# Train_Barrierx7_OPTO.net
KiCad netlist of a schematic drawn in EasyEDA
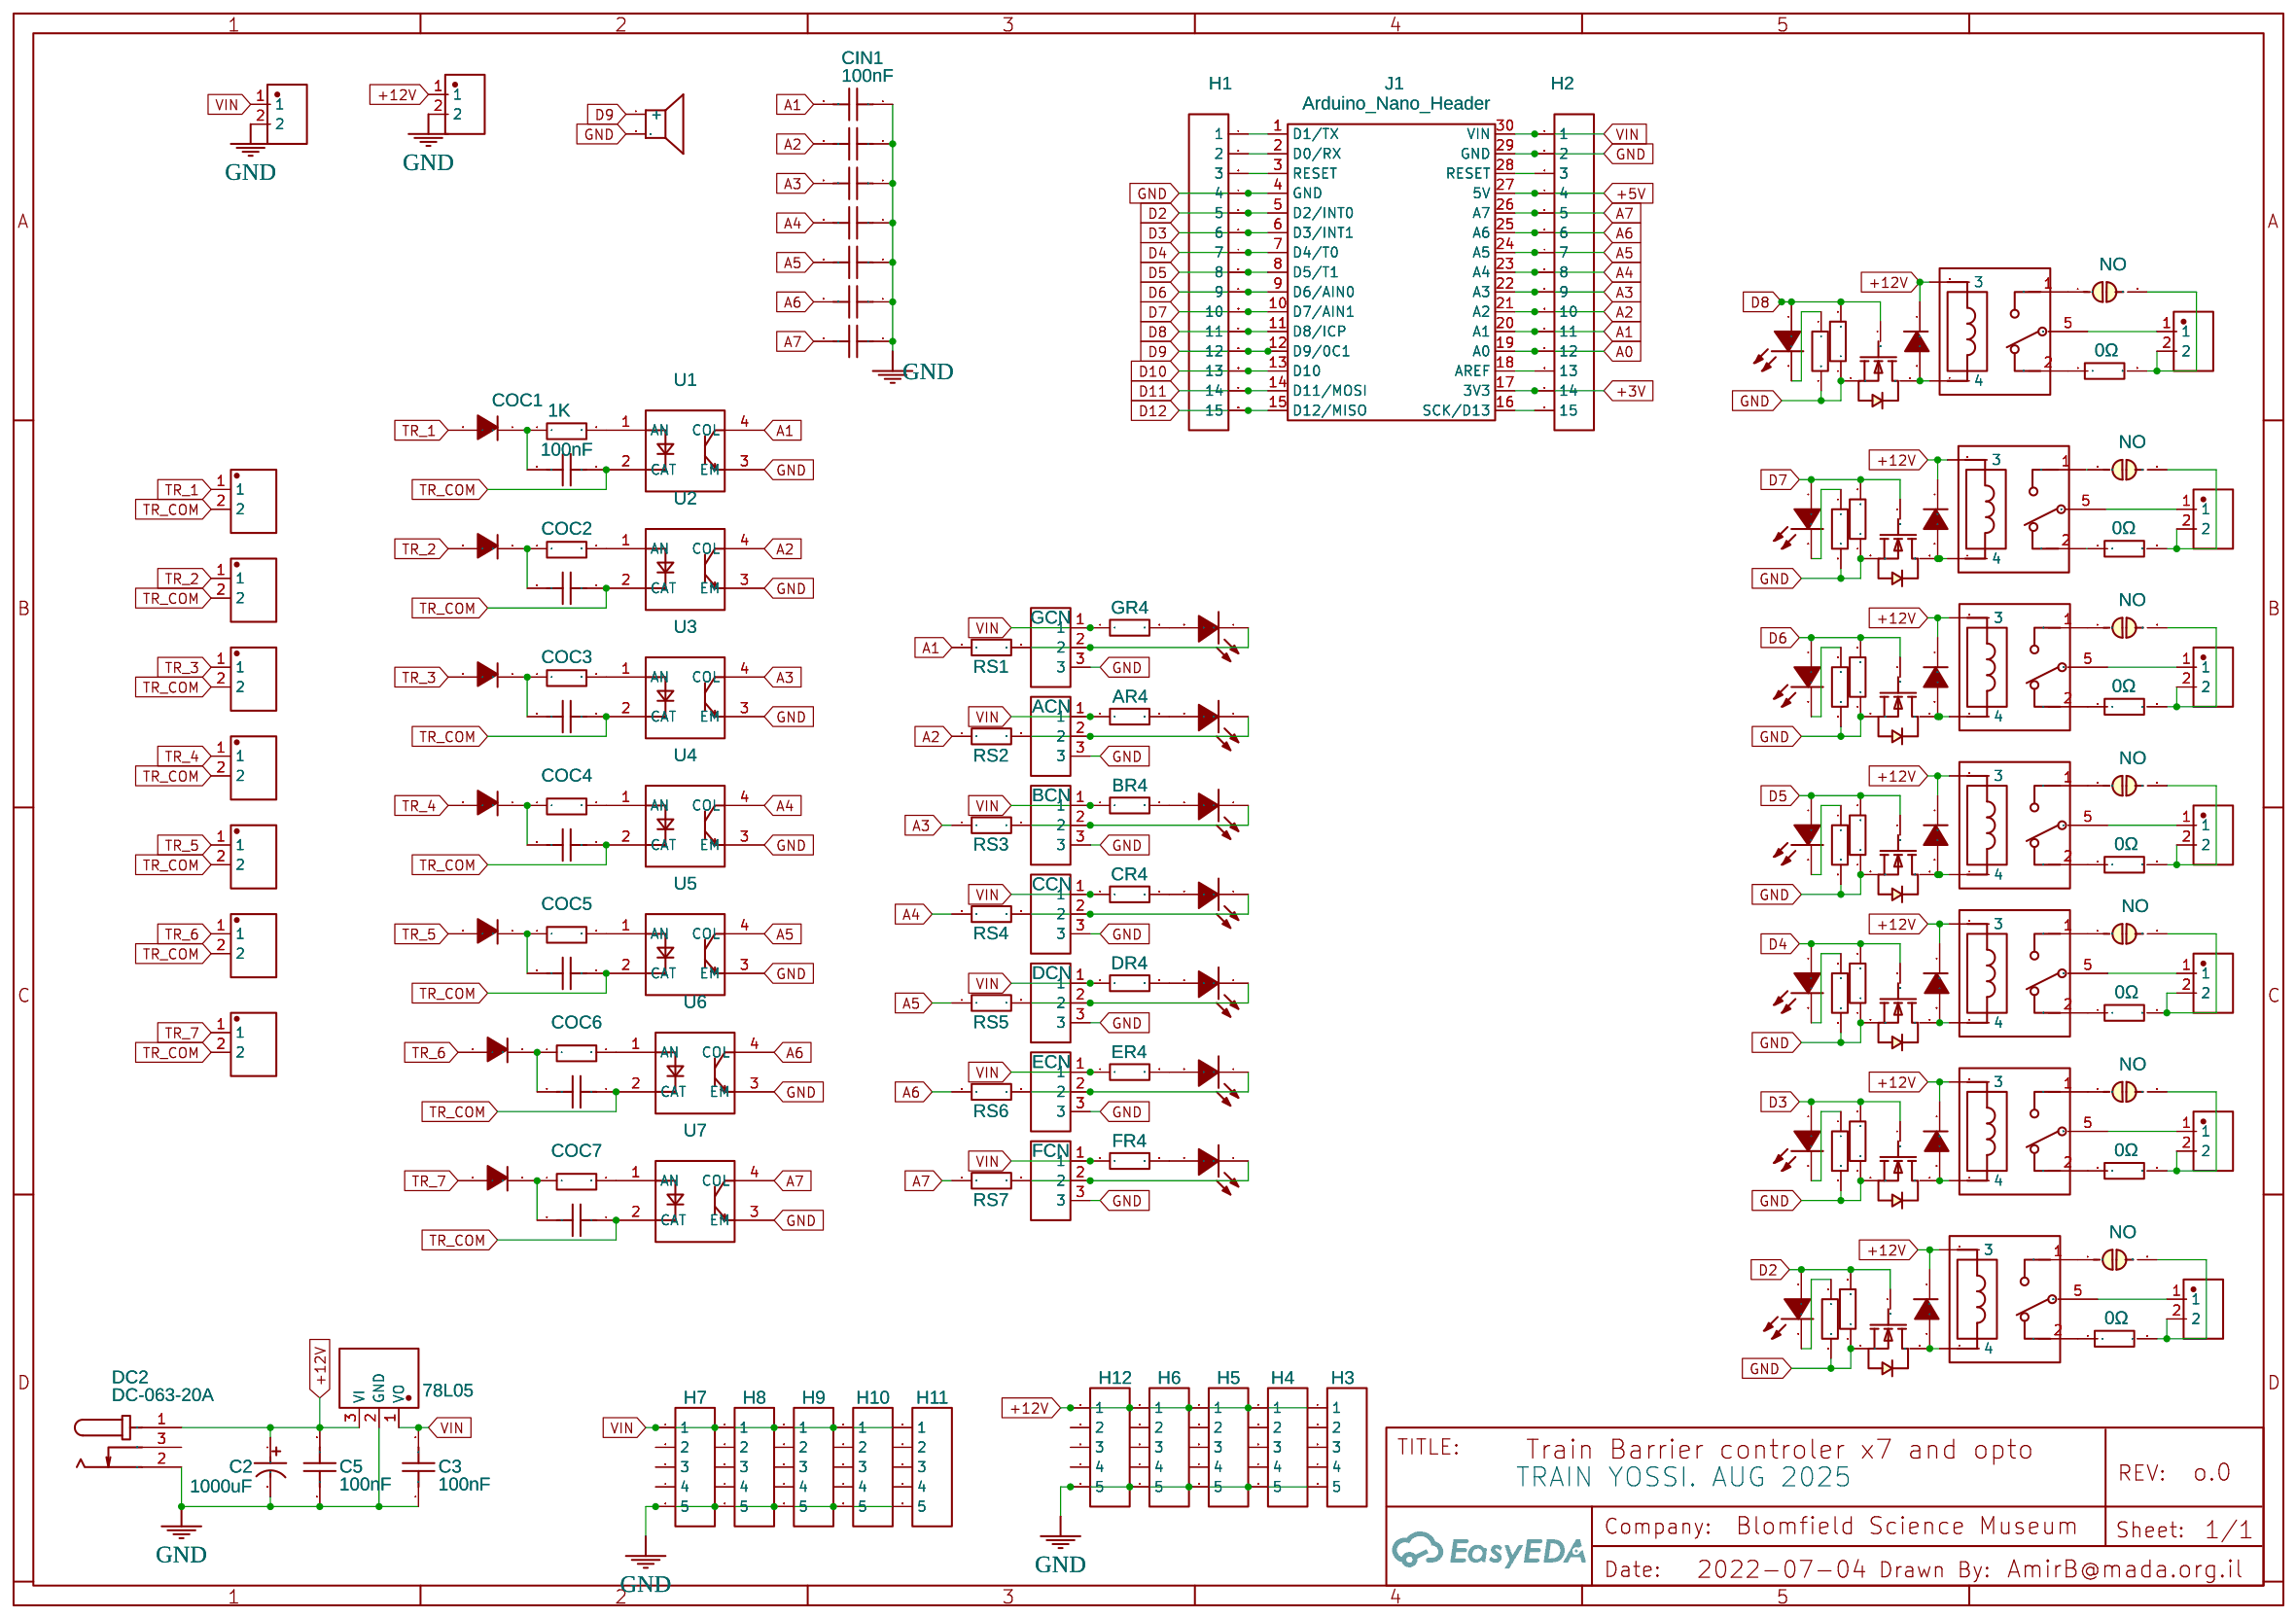
[diagram p0: schematic sheet]

(export (version "E")
  (design (tool "Eeschema 10.0.6"))
  (components
    (comp (ref "78L05")
      (value "78L05_C842819")
      (fields (field (name "BOM_Manufacturer Part") "78L05") (field (name "BOM_Supplier Part") "C842819"))
      (libsource (lib "") (part "78L05_C842819"))
    )
    (comp (ref "ACN")
      (value "FK2510")
      (fields (field (name "Manufacturer Part") "2510-3A") (field (name "Manufacturer") "BOOMELE(博穆精密)"))
      (libsource (lib "") (part "kf2510_3A_1"))
    )
    (comp (ref "ACON1")
      (value "KF2510-2A")
      (fields (field (name "BOM_Supplier Part") "C27543"))
      (libsource (lib "") (part "KF2510-2A"))
    )
    (comp (ref "ACON2")
      (value "KF2510-2A")
      (fields (field (name "BOM_Supplier Part") "C27543"))
      (libsource (lib "") (part "KF2510-2A"))
    )
    (comp (ref "ACON3")
      (value "KF2510-2A")
      (fields (field (name "BOM_Supplier Part") "C27543"))
      (libsource (lib "") (part "KF2510-2A"))
    )
    (comp (ref "ACON4")
      (value "KF2510-2A")
      (fields (field (name "BOM_Supplier Part") "C27543"))
      (libsource (lib "") (part "KF2510-2A"))
    )
    (comp (ref "ACON5")
      (value "KF2510-2A")
      (fields (field (name "BOM_Supplier Part") "C27543"))
      (libsource (lib "") (part "KF2510-2A"))
    )
    (comp (ref "ACON6")
      (value "KF2510-2A")
      (fields (field (name "BOM_Supplier Part") "C27543"))
      (libsource (lib "") (part "KF2510-2A"))
    )
    (comp (ref "ACON7")
      (value "KF2510-2A")
      (fields (field (name "BOM_Supplier Part") "C27543"))
      (libsource (lib "") (part "KF2510-2A"))
    )
    (comp (ref "ACR")
      (value "CR")
      (fields
        (field (name "BOM_Manufacturer Part") "KF301-5.0-2P")
        (field (name "BOM_Supplier Part") "C474881")
      )
      (libsource (lib "") (part "KF301-5.0-2P"))
    )
    (comp (ref "AD")
      (value "SM4007PL")
      (fields (field (name "Manufacturer") "MDD(辰达半导体)"))
      (libsource (lib "") (part "SM4007PL_6"))
    )
    (comp (ref "AJ1") (value "NO") (libsource (lib "") (part "JUMPER-SMT_2_2")))
    (comp (ref "AK")
      (value "SRA-12VDC-CL")
      (fields (field (name "Manufacturer") "松乐"))
      (libsource (lib "") (part "SRA-12VDC-CL_4"))
    )
    (comp (ref "AL")
      (value "0603White light_C2290")
      (fields (field (name "Manufacturer Part") "KT-0603W") (field (name "Manufacturer") "KENTO"))
      (libsource (lib "") (part "0603White light_C2290"))
    )
    (comp (ref "ALR")
      (value "KT-0603R")
      (fields (field (name "Manufacturer") "KENTO"))
      (libsource (lib "") (part "KT-0603R_6"))
    )
    (comp (ref "AQ")
      (value "AO3400A")
      (fields (field (name "Manufacturer") "AOS"))
      (libsource (lib "") (part "AO3400A_1"))
    )
    (comp (ref "AR1")
      (value "1K")
      (fields
        (field (name "BOM_Manufacturer Part") "0603WAF1001T5E")
        (field (name "BOM_Supplier Part") "C21190")
      )
      (libsource (lib "") (part "0603WAF1001T5E_17"))
    )
    (comp (ref "AR2")
      (value "1K")
      (fields
        (field (name "BOM_Manufacturer Part") "0603WAF1001T5E")
        (field (name "BOM_Supplier Part") "C21190")
      )
      (libsource (lib "") (part "0603WAF1001T5E_5"))
    )
    (comp (ref "AR3")
      (value "0Ω")
      (fields
        (field (name "BOM_Manufacturer Part") "0402WGF0000TCE")
        (field (name "BOM_Supplier Part") "C17168")
      )
      (libsource (lib "") (part "0402WGF0000TCE_2"))
    )
    (comp (ref "AR4")
      (value "1kΩ")
      (fields
        (field (name "BOM_Manufacturer Part") "0603WAF1001T5E")
        (field (name "BOM_Supplier Part") "C21190")
      )
      (libsource (lib "") (part "0603WAF1001T5E_20"))
    )
    (comp (ref "BCN")
      (value "FK2510")
      (fields (field (name "Manufacturer Part") "2510-3A") (field (name "Manufacturer") "BOOMELE(博穆精密)"))
      (libsource (lib "") (part "kf2510_3A_2"))
    )
    (comp (ref "BCR")
      (value "CR")
      (fields
        (field (name "BOM_Manufacturer Part") "KF301-5.0-2P")
        (field (name "BOM_Supplier Part") "C474881")
      )
      (libsource (lib "") (part "KF301-5.0-2P_6"))
    )
    (comp (ref "BD")
      (value "SM4007PL")
      (fields (field (name "Manufacturer") "MDD(辰达半导体)"))
      (libsource (lib "") (part "SM4007PL_1"))
    )
    (comp (ref "BJ1") (value "NO") (libsource (lib "") (part "JUMPER-SMT_2_6")))
    (comp (ref "BK")
      (value "SRA-12VDC-CL")
      (fields (field (name "Manufacturer") "松乐"))
      (libsource (lib "") (part "SRA-12VDC-CL"))
    )
    (comp (ref "BL")
      (value "0603White light_C2290")
      (fields (field (name "Manufacturer Part") "KT-0603W") (field (name "Manufacturer") "KENTO"))
      (libsource (lib "") (part "0603White light_C2290_6"))
    )
    (comp (ref "BLR")
      (value "KT-0603R")
      (fields (field (name "Manufacturer") "KENTO"))
      (libsource (lib "") (part "KT-0603R_1"))
    )
    (comp (ref "BQ")
      (value "AO3400A")
      (fields (field (name "Manufacturer") "AOS"))
      (libsource (lib "") (part "AO3400A_6"))
    )
    (comp (ref "BR1")
      (value "1K")
      (fields
        (field (name "BOM_Manufacturer Part") "0603WAF1001T5E")
        (field (name "BOM_Supplier Part") "C21190")
      )
      (libsource (lib "") (part "0603WAF1001T5E_1"))
    )
    (comp (ref "BR2")
      (value "1K")
      (fields
        (field (name "BOM_Manufacturer Part") "0603WAF1001T5E")
        (field (name "BOM_Supplier Part") "C21190")
      )
      (libsource (lib "") (part "0603WAF1001T5E_4"))
    )
    (comp (ref "BR3")
      (value "0Ω")
      (fields
        (field (name "BOM_Manufacturer Part") "0402WGF0000TCE")
        (field (name "BOM_Supplier Part") "C17168")
      )
      (libsource (lib "") (part "0402WGF0000TCE_4"))
    )
    (comp (ref "BR4")
      (value "1kΩ")
      (fields
        (field (name "BOM_Manufacturer Part") "0603WAF1001T5E")
        (field (name "BOM_Supplier Part") "C21190")
      )
      (libsource (lib "") (part "0603WAF1001T5E_14"))
    )
    (comp (ref "BUZZER1")
      (value "BUZZER-12X9")
      (fields (field (name "Manufacturer Part") "buzzer-12X9"))
      (libsource (lib "") (part "BUZZER-12X9"))
    )
    (comp (ref "C2")
      (value "1000uF")
      (fields (field (name "BOM_Manufacturer Part") "1000uF 50V") (field (name "BOM_Supplier Part") "C18104"))
      (libsource (lib "") (part "1000uF 50V"))
    )
    (comp (ref "C3")
      (value "100nF")
      (fields
        (field (name "BOM_Manufacturer Part") "CC0603KRX7R9BB104")
        (field (name "BOM_Supplier Part") "C14663")
      )
      (libsource (lib "") (part "CC0603KRX7R9BB104_1"))
    )
    (comp (ref "C5")
      (value "100nF")
      (fields
        (field (name "BOM_Manufacturer Part") "CC0603KRX7R9BB104")
        (field (name "BOM_Supplier Part") "C14663")
      )
      (libsource (lib "") (part "CC0603KRX7R9BB104_1"))
    )
    (comp (ref "CCN")
      (value "FK2510")
      (fields (field (name "Manufacturer Part") "2510-3A") (field (name "Manufacturer") "BOOMELE(博穆精密)"))
      (libsource (lib "") (part "kf2510_3A"))
    )
    (comp (ref "CCR")
      (value "CR")
      (fields
        (field (name "BOM_Manufacturer Part") "KF301-5.0-2P")
        (field (name "BOM_Supplier Part") "C474881")
      )
      (libsource (lib "") (part "KF301-5.0-2P_2"))
    )
    (comp (ref "CD")
      (value "SM4007PL")
      (fields (field (name "Manufacturer") "MDD(辰达半导体)"))
      (libsource (lib "") (part "SM4007PL_7"))
    )
    (comp (ref "CIN1")
      (value "100nF")
      (fields
        (field (name "BOM_Manufacturer Part") "CC0603KRX7R9BB104")
        (field (name "BOM_Supplier Part") "C14663")
      )
      (libsource (lib "") (part "CC0603KRX7R9BB104_2"))
    )
    (comp (ref "CIN2")
      (value "100nF")
      (fields
        (field (name "BOM_Manufacturer Part") "CC0603KRX7R9BB104")
        (field (name "BOM_Supplier Part") "C14663")
      )
      (libsource (lib "") (part "CC0603KRX7R9BB104_2"))
    )
    (comp (ref "CIN3")
      (value "100nF")
      (fields
        (field (name "BOM_Manufacturer Part") "CC0603KRX7R9BB104")
        (field (name "BOM_Supplier Part") "C14663")
      )
      (libsource (lib "") (part "CC0603KRX7R9BB104_2"))
    )
    (comp (ref "CIN4")
      (value "100nF")
      (fields
        (field (name "BOM_Manufacturer Part") "CC0603KRX7R9BB104")
        (field (name "BOM_Supplier Part") "C14663")
      )
      (libsource (lib "") (part "CC0603KRX7R9BB104_2"))
    )
    (comp (ref "CIN5")
      (value "100nF")
      (fields
        (field (name "BOM_Manufacturer Part") "CC0603KRX7R9BB104")
        (field (name "BOM_Supplier Part") "C14663")
      )
      (libsource (lib "") (part "CC0603KRX7R9BB104_2"))
    )
    (comp (ref "CIN6")
      (value "100nF")
      (fields
        (field (name "BOM_Manufacturer Part") "CC0603KRX7R9BB104")
        (field (name "BOM_Supplier Part") "C14663")
      )
      (libsource (lib "") (part "CC0603KRX7R9BB104_2"))
    )
    (comp (ref "CIN7")
      (value "100nF")
      (fields
        (field (name "BOM_Manufacturer Part") "CC0603KRX7R9BB104")
        (field (name "BOM_Supplier Part") "C14663")
      )
      (libsource (lib "") (part "CC0603KRX7R9BB104_2"))
    )
    (comp (ref "CJ1") (value "NO") (libsource (lib "") (part "JUMPER-SMT_2_3")))
    (comp (ref "CK")
      (value "SRA-12VDC-CL")
      (fields (field (name "Manufacturer") "松乐"))
      (libsource (lib "") (part "SRA-12VDC-CL_5"))
    )
    (comp (ref "CL")
      (value "0603White light_C2290")
      (fields (field (name "Manufacturer Part") "KT-0603W") (field (name "Manufacturer") "KENTO"))
      (libsource (lib "") (part "0603White light_C2290_1"))
    )
    (comp (ref "CLR")
      (value "KT-0603R")
      (fields (field (name "Manufacturer") "KENTO"))
      (libsource (lib "") (part "KT-0603R"))
    )
    (comp (ref "COC1")
      (value "100nF")
      (fields
        (field (name "BOM_Manufacturer Part") "CC0603KRX7R9BB104")
        (field (name "BOM_Supplier Part") "C14663")
      )
      (libsource (lib "") (part "CC0603KRX7R9BB104"))
    )
    (comp (ref "COC2")
      (value "100nF")
      (fields
        (field (name "BOM_Manufacturer Part") "CC0603KRX7R9BB104")
        (field (name "BOM_Supplier Part") "C14663")
      )
      (libsource (lib "") (part "CC0603KRX7R9BB104"))
    )
    (comp (ref "COC3")
      (value "100nF")
      (fields
        (field (name "BOM_Manufacturer Part") "CC0603KRX7R9BB104")
        (field (name "BOM_Supplier Part") "C14663")
      )
      (libsource (lib "") (part "CC0603KRX7R9BB104"))
    )
    (comp (ref "COC4")
      (value "100nF")
      (fields
        (field (name "BOM_Manufacturer Part") "CC0603KRX7R9BB104")
        (field (name "BOM_Supplier Part") "C14663")
      )
      (libsource (lib "") (part "CC0603KRX7R9BB104"))
    )
    (comp (ref "COC5")
      (value "100nF")
      (fields
        (field (name "BOM_Manufacturer Part") "CC0603KRX7R9BB104")
        (field (name "BOM_Supplier Part") "C14663")
      )
      (libsource (lib "") (part "CC0603KRX7R9BB104"))
    )
    (comp (ref "COC6")
      (value "100nF")
      (fields
        (field (name "BOM_Manufacturer Part") "CC0603KRX7R9BB104")
        (field (name "BOM_Supplier Part") "C14663")
      )
      (libsource (lib "") (part "CC0603KRX7R9BB104"))
    )
    (comp (ref "COC7")
      (value "100nF")
      (fields
        (field (name "BOM_Manufacturer Part") "CC0603KRX7R9BB104")
        (field (name "BOM_Supplier Part") "C14663")
      )
      (libsource (lib "") (part "CC0603KRX7R9BB104"))
    )
    (comp (ref "CQ")
      (value "AO3400A")
      (fields (field (name "Manufacturer") "AOS"))
      (libsource (lib "") (part "AO3400A_3"))
    )
    (comp (ref "CR1")
      (value "1K")
      (fields
        (field (name "BOM_Manufacturer Part") "0603WAF1001T5E")
        (field (name "BOM_Supplier Part") "C21190")
      )
      (libsource (lib "") (part "0603WAF1001T5E_15"))
    )
    (comp (ref "CR2")
      (value "1K")
      (fields
        (field (name "BOM_Manufacturer Part") "0603WAF1001T5E")
        (field (name "BOM_Supplier Part") "C21190")
      )
      (libsource (lib "") (part "0603WAF1001T5E_16"))
    )
    (comp (ref "CR3")
      (value "0Ω")
      (fields
        (field (name "BOM_Manufacturer Part") "0402WGF0000TCE")
        (field (name "BOM_Supplier Part") "C17168")
      )
      (libsource (lib "") (part "0402WGF0000TCE_1"))
    )
    (comp (ref "CR4")
      (value "1kΩ")
      (fields
        (field (name "BOM_Manufacturer Part") "0603WAF1001T5E")
        (field (name "BOM_Supplier Part") "C21190")
      )
      (libsource (lib "") (part "0603WAF1001T5E_2"))
    )
    (comp (ref "CR5V")
      (value "CR5V")
      (fields
        (field (name "BOM_Manufacturer Part") "KF301-5.0-2P")
        (field (name "BOM_Supplier Part") "C474881")
      )
      (libsource (lib "") (part "KF301-5.0-2P_4"))
    )
    (comp (ref "CR12V")
      (value "CR12V")
      (fields
        (field (name "BOM_Manufacturer Part") "KF301-5.0-2P")
        (field (name "BOM_Supplier Part") "C474881")
      )
      (libsource (lib "") (part "KF301-5.0-2P_3"))
    )
    (comp (ref "DC2")
      (value "DC-063-20A")
      (fields (field (name "BOM_Supplier Part") "C707268"))
      (libsource (lib "") (part "DC-063-20A"))
    )
    (comp (ref "DCN")
      (value "FK2510")
      (fields (field (name "Manufacturer Part") "2510-3A") (field (name "Manufacturer") "BOOMELE(博穆精密)"))
      (libsource (lib "") (part "kf2510_3A_5"))
    )
    (comp (ref "DCR")
      (value "CR")
      (fields
        (field (name "BOM_Manufacturer Part") "KF301-5.0-2P")
        (field (name "BOM_Supplier Part") "C474881")
      )
      (libsource (lib "") (part "KF301-5.0-2P_7"))
    )
    (comp (ref "DD")
      (value "SM4007PL")
      (fields (field (name "Manufacturer") "MDD(辰达半导体)"))
      (libsource (lib "") (part "SM4007PL_2"))
    )
    (comp (ref "DJ1") (value "NO") (libsource (lib "") (part "JUMPER-SMT_2_1")))
    (comp (ref "DK")
      (value "SRA-12VDC-CL")
      (fields (field (name "Manufacturer") "松乐"))
      (libsource (lib "") (part "SRA-12VDC-CL_1"))
    )
    (comp (ref "DL")
      (value "0603White light_C2290")
      (fields (field (name "Manufacturer Part") "KT-0603W") (field (name "Manufacturer") "KENTO"))
      (libsource (lib "") (part "0603White light_C2290_2"))
    )
    (comp (ref "DLR")
      (value "KT-0603R")
      (fields (field (name "Manufacturer") "KENTO"))
      (libsource (lib "") (part "KT-0603R_2"))
    )
    (comp (ref "DOC1")
      (value "SM4007PL")
      (fields (field (name "Manufacturer") "MDD(辰达半导体)"))
      (libsource (lib "") (part "SM4007PL"))
    )
    (comp (ref "DOC2")
      (value "SM4007PL")
      (fields (field (name "Manufacturer") "MDD(辰达半导体)"))
      (libsource (lib "") (part "SM4007PL"))
    )
    (comp (ref "DOC3")
      (value "SM4007PL")
      (fields (field (name "Manufacturer") "MDD(辰达半导体)"))
      (libsource (lib "") (part "SM4007PL"))
    )
    (comp (ref "DOC4")
      (value "SM4007PL")
      (fields (field (name "Manufacturer") "MDD(辰达半导体)"))
      (libsource (lib "") (part "SM4007PL"))
    )
    (comp (ref "DOC5")
      (value "SM4007PL")
      (fields (field (name "Manufacturer") "MDD(辰达半导体)"))
      (libsource (lib "") (part "SM4007PL"))
    )
    (comp (ref "DOC6")
      (value "SM4007PL")
      (fields (field (name "Manufacturer") "MDD(辰达半导体)"))
      (libsource (lib "") (part "SM4007PL"))
    )
    (comp (ref "DOC7")
      (value "SM4007PL")
      (fields (field (name "Manufacturer") "MDD(辰达半导体)"))
      (libsource (lib "") (part "SM4007PL"))
    )
    (comp (ref "DQ")
      (value "AO3400A")
      (fields (field (name "Manufacturer") "AOS"))
      (libsource (lib "") (part "AO3400A_4"))
    )
    (comp (ref "DR1")
      (value "1K")
      (fields
        (field (name "BOM_Manufacturer Part") "0603WAF1001T5E")
        (field (name "BOM_Supplier Part") "C21190")
      )
      (libsource (lib "") (part "0603WAF1001T5E_9"))
    )
    (comp (ref "DR2")
      (value "1K")
      (fields
        (field (name "BOM_Manufacturer Part") "0603WAF1001T5E")
        (field (name "BOM_Supplier Part") "C21190")
      )
      (libsource (lib "") (part "0603WAF1001T5E_12"))
    )
    (comp (ref "DR3")
      (value "0Ω")
      (fields
        (field (name "BOM_Manufacturer Part") "0402WGF0000TCE")
        (field (name "BOM_Supplier Part") "C17168")
      )
      (libsource (lib "") (part "0402WGF0000TCE"))
    )
    (comp (ref "DR4")
      (value "1kΩ")
      (fields
        (field (name "BOM_Manufacturer Part") "0603WAF1001T5E")
        (field (name "BOM_Supplier Part") "C21190")
      )
      (libsource (lib "") (part "0603WAF1001T5E_6"))
    )
    (comp (ref "ECN")
      (value "FK2510")
      (fields (field (name "Manufacturer Part") "2510-3A") (field (name "Manufacturer") "BOOMELE(博穆精密)"))
      (libsource (lib "") (part "kf2510_3A_3"))
    )
    (comp (ref "ECR")
      (value "CR")
      (fields
        (field (name "BOM_Manufacturer Part") "KF301-5.0-2P")
        (field (name "BOM_Supplier Part") "C474881")
      )
      (libsource (lib "") (part "KF301-5.0-2P_5"))
    )
    (comp (ref "ED")
      (value "SM4007PL")
      (fields (field (name "Manufacturer") "MDD(辰达半导体)"))
      (libsource (lib "") (part "SM4007PL_3"))
    )
    (comp (ref "EJ1") (value "NO") (libsource (lib "") (part "JUMPER-SMT_2")))
    (comp (ref "EK")
      (value "SRA-12VDC-CL")
      (fields (field (name "Manufacturer") "松乐"))
      (libsource (lib "") (part "SRA-12VDC-CL_2"))
    )
    (comp (ref "EL")
      (value "0603White light_C2290")
      (fields (field (name "Manufacturer Part") "KT-0603W") (field (name "Manufacturer") "KENTO"))
      (libsource (lib "") (part "0603White light_C2290_5"))
    )
    (comp (ref "ELR")
      (value "KT-0603R")
      (fields (field (name "Manufacturer") "KENTO"))
      (libsource (lib "") (part "KT-0603R_3"))
    )
    (comp (ref "EQ")
      (value "AO3400A")
      (fields (field (name "Manufacturer") "AOS"))
      (libsource (lib "") (part "AO3400A_2"))
    )
    (comp (ref "ER1")
      (value "1K")
      (fields
        (field (name "BOM_Manufacturer Part") "0603WAF1001T5E")
        (field (name "BOM_Supplier Part") "C21190")
      )
      (libsource (lib "") (part "0603WAF1001T5E_22"))
    )
    (comp (ref "ER2")
      (value "1K")
      (fields
        (field (name "BOM_Manufacturer Part") "0603WAF1001T5E")
        (field (name "BOM_Supplier Part") "C21190")
      )
      (libsource (lib "") (part "0603WAF1001T5E_10"))
    )
    (comp (ref "ER3")
      (value "0Ω")
      (fields
        (field (name "BOM_Manufacturer Part") "0402WGF0000TCE")
        (field (name "BOM_Supplier Part") "C17168")
      )
      (libsource (lib "") (part "0402WGF0000TCE_3"))
    )
    (comp (ref "ER4")
      (value "1kΩ")
      (fields
        (field (name "BOM_Manufacturer Part") "0603WAF1001T5E")
        (field (name "BOM_Supplier Part") "C21190")
      )
      (libsource (lib "") (part "0603WAF1001T5E_19"))
    )
    (comp (ref "FCN")
      (value "FK2510")
      (fields (field (name "Manufacturer Part") "2510-3A") (field (name "Manufacturer") "BOOMELE(博穆精密)"))
      (libsource (lib "") (part "kf2510_3A_6"))
    )
    (comp (ref "FCR")
      (value "CR")
      (fields
        (field (name "BOM_Manufacturer Part") "KF301-5.0-2P")
        (field (name "BOM_Supplier Part") "C474881")
      )
      (libsource (lib "") (part "KF301-5.0-2P_8"))
    )
    (comp (ref "FD")
      (value "SM4007PL")
      (fields (field (name "Manufacturer") "MDD(辰达半导体)"))
      (libsource (lib "") (part "SM4007PL_5"))
    )
    (comp (ref "FJ1") (value "NO") (libsource (lib "") (part "JUMPER-SMT_2_4")))
    (comp (ref "FK")
      (value "SRA-12VDC-CL")
      (fields (field (name "Manufacturer") "松乐"))
      (libsource (lib "") (part "SRA-12VDC-CL_3"))
    )
    (comp (ref "FL")
      (value "0603White light_C2290")
      (fields (field (name "Manufacturer Part") "KT-0603W") (field (name "Manufacturer") "KENTO"))
      (libsource (lib "") (part "0603White light_C2290_3"))
    )
    (comp (ref "FLR")
      (value "KT-0603R")
      (fields (field (name "Manufacturer") "KENTO"))
      (libsource (lib "") (part "KT-0603R_5"))
    )
    (comp (ref "FQ")
      (value "AO3400A")
      (fields (field (name "Manufacturer") "AOS"))
      (libsource (lib "") (part "AO3400A"))
    )
    (comp (ref "FR1")
      (value "1K")
      (fields
        (field (name "BOM_Manufacturer Part") "0603WAF1001T5E")
        (field (name "BOM_Supplier Part") "C21190")
      )
      (libsource (lib "") (part "0603WAF1001T5E_13"))
    )
    (comp (ref "FR2")
      (value "1K")
      (fields
        (field (name "BOM_Manufacturer Part") "0603WAF1001T5E")
        (field (name "BOM_Supplier Part") "C21190")
      )
      (libsource (lib "") (part "0603WAF1001T5E_7"))
    )
    (comp (ref "FR3")
      (value "0Ω")
      (fields
        (field (name "BOM_Manufacturer Part") "0402WGF0000TCE")
        (field (name "BOM_Supplier Part") "C17168")
      )
      (libsource (lib "") (part "0402WGF0000TCE_6"))
    )
    (comp (ref "FR4")
      (value "1kΩ")
      (fields
        (field (name "BOM_Manufacturer Part") "0603WAF1001T5E")
        (field (name "BOM_Supplier Part") "C21190")
      )
      (libsource (lib "") (part "0603WAF1001T5E_8"))
    )
    (comp (ref "GCN")
      (value "FK2510")
      (fields (field (name "Manufacturer Part") "2510-3A") (field (name "Manufacturer") "BOOMELE(博穆精密)"))
      (libsource (lib "") (part "kf2510_3A_4"))
    )
    (comp (ref "GCR")
      (value "CR")
      (fields
        (field (name "BOM_Manufacturer Part") "KF301-5.0-2P")
        (field (name "BOM_Supplier Part") "C474881")
      )
      (libsource (lib "") (part "KF301-5.0-2P_1"))
    )
    (comp (ref "GD")
      (value "SM4007PL")
      (fields (field (name "Manufacturer") "MDD(辰达半导体)"))
      (libsource (lib "") (part "SM4007PL_4"))
    )
    (comp (ref "GJ1") (value "NO") (libsource (lib "") (part "JUMPER-SMT_2_5")))
    (comp (ref "GK")
      (value "SRA-12VDC-CL")
      (fields (field (name "Manufacturer") "松乐"))
      (libsource (lib "") (part "SRA-12VDC-CL_6"))
    )
    (comp (ref "GL")
      (value "0603White light_C2290")
      (fields (field (name "Manufacturer Part") "KT-0603W") (field (name "Manufacturer") "KENTO"))
      (libsource (lib "") (part "0603White light_C2290_4"))
    )
    (comp (ref "GLR")
      (value "KT-0603R")
      (fields (field (name "Manufacturer") "KENTO"))
      (libsource (lib "") (part "KT-0603R_4"))
    )
    (comp (ref "GQ")
      (value "AO3400A")
      (fields (field (name "Manufacturer") "AOS"))
      (libsource (lib "") (part "AO3400A_5"))
    )
    (comp (ref "GR1")
      (value "1K")
      (fields
        (field (name "BOM_Manufacturer Part") "0603WAF1001T5E")
        (field (name "BOM_Supplier Part") "C21190")
      )
      (libsource (lib "") (part "0603WAF1001T5E_11"))
    )
    (comp (ref "GR2")
      (value "1K")
      (fields
        (field (name "BOM_Manufacturer Part") "0603WAF1001T5E")
        (field (name "BOM_Supplier Part") "C21190")
      )
      (libsource (lib "") (part "0603WAF1001T5E_21"))
    )
    (comp (ref "GR3")
      (value "0Ω")
      (fields
        (field (name "BOM_Manufacturer Part") "0402WGF0000TCE")
        (field (name "BOM_Supplier Part") "C17168")
      )
      (libsource (lib "") (part "0402WGF0000TCE_5"))
    )
    (comp (ref "GR4")
      (value "1kΩ")
      (fields
        (field (name "BOM_Manufacturer Part") "0603WAF1001T5E")
        (field (name "BOM_Supplier Part") "C21190")
      )
      (libsource (lib "") (part "0603WAF1001T5E_18"))
    )
    (comp (ref "H1")
      (value "HDR-F-2.54_1x15")
      (fields (field (name "BOM_Supplier Part") "C124408"))
      (libsource (lib "") (part "HDR-F-2.54_1x15"))
    )
    (comp (ref "H2")
      (value "HDR-F-2.54_1x15")
      (fields (field (name "BOM_Supplier Part") "C124408"))
      (libsource (lib "") (part "HDR-F-2.54_1x15_1"))
    )
    (comp (ref "H3")
      (value "HDR-F-2.54_1x5")
      (fields (field (name "BOM_Supplier Part") "C50950"))
      (libsource (lib "") (part "HDR-F-2.54_1x5"))
    )
    (comp (ref "H4")
      (value "HDR-F-2.54_1x5")
      (fields (field (name "BOM_Supplier Part") "C50950"))
      (libsource (lib "") (part "HDR-F-2.54_1x5"))
    )
    (comp (ref "H5")
      (value "HDR-F-2.54_1x5")
      (fields (field (name "BOM_Supplier Part") "C50950"))
      (libsource (lib "") (part "HDR-F-2.54_1x5"))
    )
    (comp (ref "H6")
      (value "HDR-F-2.54_1x5")
      (fields (field (name "BOM_Supplier Part") "C50950"))
      (libsource (lib "") (part "HDR-F-2.54_1x5"))
    )
    (comp (ref "H7")
      (value "HDR-F-2.54_1x5")
      (fields (field (name "BOM_Supplier Part") "C50950"))
      (libsource (lib "") (part "HDR-F-2.54_1x5"))
    )
    (comp (ref "H8")
      (value "HDR-F-2.54_1x5")
      (fields (field (name "BOM_Supplier Part") "C50950"))
      (libsource (lib "") (part "HDR-F-2.54_1x5"))
    )
    (comp (ref "H9")
      (value "HDR-F-2.54_1x5")
      (fields (field (name "BOM_Supplier Part") "C50950"))
      (libsource (lib "") (part "HDR-F-2.54_1x5"))
    )
    (comp (ref "H10")
      (value "HDR-F-2.54_1x5")
      (fields (field (name "BOM_Supplier Part") "C50950"))
      (libsource (lib "") (part "HDR-F-2.54_1x5"))
    )
    (comp (ref "H11")
      (value "HDR-F-2.54_1x5")
      (fields (field (name "BOM_Supplier Part") "C50950"))
      (libsource (lib "") (part "HDR-F-2.54_1x5"))
    )
    (comp (ref "H12")
      (value "HDR-F-2.54_1x5")
      (fields (field (name "BOM_Supplier Part") "C50950"))
      (libsource (lib "") (part "HDR-F-2.54_1x5"))
    )
    (comp (ref "J1") (value "Arduino_Nano_Header") (libsource (lib "") (part "Arduino_Nano_Header")))
    (comp (ref "ROC1")
      (value "1K")
      (fields
        (field (name "BOM_Manufacturer Part") "0603WAF1001T5E")
        (field (name "BOM_Supplier Part") "C21190")
      )
      (libsource (lib "") (part "0603WAF1001T5E_3"))
    )
    (comp (ref "ROC2")
      (value "1K")
      (fields
        (field (name "BOM_Manufacturer Part") "0603WAF1001T5E")
        (field (name "BOM_Supplier Part") "C21190")
      )
      (libsource (lib "") (part "0603WAF1001T5E_3"))
    )
    (comp (ref "ROC3")
      (value "1K")
      (fields
        (field (name "BOM_Manufacturer Part") "0603WAF1001T5E")
        (field (name "BOM_Supplier Part") "C21190")
      )
      (libsource (lib "") (part "0603WAF1001T5E_3"))
    )
    (comp (ref "ROC4")
      (value "1K")
      (fields
        (field (name "BOM_Manufacturer Part") "0603WAF1001T5E")
        (field (name "BOM_Supplier Part") "C21190")
      )
      (libsource (lib "") (part "0603WAF1001T5E_3"))
    )
    (comp (ref "ROC5")
      (value "1K")
      (fields
        (field (name "BOM_Manufacturer Part") "0603WAF1001T5E")
        (field (name "BOM_Supplier Part") "C21190")
      )
      (libsource (lib "") (part "0603WAF1001T5E_3"))
    )
    (comp (ref "ROC6")
      (value "1K")
      (fields
        (field (name "BOM_Manufacturer Part") "0603WAF1001T5E")
        (field (name "BOM_Supplier Part") "C21190")
      )
      (libsource (lib "") (part "0603WAF1001T5E_3"))
    )
    (comp (ref "ROC7")
      (value "1K")
      (fields
        (field (name "BOM_Manufacturer Part") "0603WAF1001T5E")
        (field (name "BOM_Supplier Part") "C21190")
      )
      (libsource (lib "") (part "0603WAF1001T5E_3"))
    )
    (comp (ref "RS1")
      (value "1kΩ")
      (fields
        (field (name "BOM_Manufacturer Part") "0603WAF1001T5E")
        (field (name "BOM_Supplier Part") "C21190")
      )
      (libsource (lib "") (part "0603WAF1001T5E"))
    )
    (comp (ref "RS2")
      (value "1kΩ")
      (fields
        (field (name "BOM_Manufacturer Part") "0603WAF1001T5E")
        (field (name "BOM_Supplier Part") "C21190")
      )
      (libsource (lib "") (part "0603WAF1001T5E"))
    )
    (comp (ref "RS3")
      (value "1kΩ")
      (fields
        (field (name "BOM_Manufacturer Part") "0603WAF1001T5E")
        (field (name "BOM_Supplier Part") "C21190")
      )
      (libsource (lib "") (part "0603WAF1001T5E"))
    )
    (comp (ref "RS4")
      (value "1kΩ")
      (fields
        (field (name "BOM_Manufacturer Part") "0603WAF1001T5E")
        (field (name "BOM_Supplier Part") "C21190")
      )
      (libsource (lib "") (part "0603WAF1001T5E"))
    )
    (comp (ref "RS5")
      (value "1kΩ")
      (fields
        (field (name "BOM_Manufacturer Part") "0603WAF1001T5E")
        (field (name "BOM_Supplier Part") "C21190")
      )
      (libsource (lib "") (part "0603WAF1001T5E"))
    )
    (comp (ref "RS6")
      (value "1kΩ")
      (fields
        (field (name "BOM_Manufacturer Part") "0603WAF1001T5E")
        (field (name "BOM_Supplier Part") "C21190")
      )
      (libsource (lib "") (part "0603WAF1001T5E"))
    )
    (comp (ref "RS7")
      (value "1kΩ")
      (fields
        (field (name "BOM_Manufacturer Part") "0603WAF1001T5E")
        (field (name "BOM_Supplier Part") "C21190")
      )
      (libsource (lib "") (part "0603WAF1001T5E"))
    )
    (comp (ref "U1")
      (value "LTV-217-B-G")
      (fields (field (name "Manufacturer") "LITEON(光宝)"))
      (libsource (lib "") (part "LTV-217-B-G"))
    )
    (comp (ref "U2")
      (value "LTV-217-B-G")
      (fields (field (name "Manufacturer") "LITEON(光宝)"))
      (libsource (lib "") (part "LTV-217-B-G"))
    )
    (comp (ref "U3")
      (value "LTV-217-B-G")
      (fields (field (name "Manufacturer") "LITEON(光宝)"))
      (libsource (lib "") (part "LTV-217-B-G"))
    )
    (comp (ref "U4")
      (value "LTV-217-B-G")
      (fields (field (name "Manufacturer") "LITEON(光宝)"))
      (libsource (lib "") (part "LTV-217-B-G"))
    )
    (comp (ref "U5")
      (value "LTV-217-B-G")
      (fields (field (name "Manufacturer") "LITEON(光宝)"))
      (libsource (lib "") (part "LTV-217-B-G"))
    )
    (comp (ref "U6")
      (value "LTV-217-B-G")
      (fields (field (name "Manufacturer") "LITEON(光宝)"))
      (libsource (lib "") (part "LTV-217-B-G"))
    )
    (comp (ref "U7")
      (value "LTV-217-B-G")
      (fields (field (name "Manufacturer") "LITEON(光宝)"))
      (libsource (lib "") (part "LTV-217-B-G"))
    )
  )
  (nets
    (net (code "1") (name "+3V") (class "Default")
      (node (ref "H2") (pin "14") (pinfunction "14_14") (pintype "unspecified"))
      (node (ref "J1") (pin "17") (pinfunction "3V3_17") (pintype "unspecified"))
    )
    (net (code "2") (name "+5V") (class "Default")
      (node (ref "H2") (pin "4") (pinfunction "4_4") (pintype "unspecified"))
      (node (ref "J1") (pin "27") (pinfunction "5V_27") (pintype "unspecified"))
    )
    (net (code "3") (name "+12V") (class "Default")
      (node (ref "78L05") (pin "3") (pinfunction "VI_3") (pintype "unspecified"))
      (node (ref "AD") (pin "1") (pinfunction "C_1") (pintype "unspecified"))
      (node (ref "AK") (pin "3") (pinfunction "3_3") (pintype "unspecified"))
      (node (ref "BD") (pin "1") (pinfunction "C_1") (pintype "unspecified"))
      (node (ref "BK") (pin "3") (pinfunction "3_3") (pintype "unspecified"))
      (node (ref "C2") (pin "1") (pinfunction "1_1") (pintype "input"))
      (node (ref "C5") (pin "2") (pinfunction "2_2") (pintype "unspecified"))
      (node (ref "CD") (pin "1") (pinfunction "C_1") (pintype "unspecified"))
      (node (ref "CK") (pin "3") (pinfunction "3_3") (pintype "unspecified"))
      (node (ref "CR12V") (pin "1") (pinfunction "1_1") (pintype "unspecified"))
      (node (ref "DC2") (pin "1") (pinfunction "1_1") (pintype "unspecified"))
      (node (ref "DD") (pin "1") (pinfunction "C_1") (pintype "unspecified"))
      (node (ref "DK") (pin "3") (pinfunction "3_3") (pintype "unspecified"))
      (node (ref "ED") (pin "1") (pinfunction "C_1") (pintype "unspecified"))
      (node (ref "EK") (pin "3") (pinfunction "3_3") (pintype "unspecified"))
      (node (ref "FD") (pin "1") (pinfunction "C_1") (pintype "unspecified"))
      (node (ref "FK") (pin "3") (pinfunction "3_3") (pintype "unspecified"))
      (node (ref "GD") (pin "1") (pinfunction "C_1") (pintype "unspecified"))
      (node (ref "GK") (pin "3") (pinfunction "3_3") (pintype "unspecified"))
      (node (ref "H12") (pin "1") (pinfunction "1_1") (pintype "unspecified"))
      (node (ref "H3") (pin "1") (pinfunction "1_1") (pintype "unspecified"))
      (node (ref "H4") (pin "1") (pinfunction "1_1") (pintype "unspecified"))
      (node (ref "H5") (pin "1") (pinfunction "1_1") (pintype "unspecified"))
      (node (ref "H6") (pin "1") (pinfunction "1_1") (pintype "unspecified"))
    )
    (net (code "4") (name "A0") (class "Default")
      (node (ref "H2") (pin "12") (pinfunction "12_12") (pintype "unspecified"))
      (node (ref "J1") (pin "19") (pinfunction "A0_19") (pintype "unspecified"))
    )
    (net (code "5") (name "A1") (class "Default")
      (node (ref "CIN1") (pin "2") (pinfunction "2_2") (pintype "unspecified"))
      (node (ref "H2") (pin "11") (pinfunction "11_11") (pintype "unspecified"))
      (node (ref "J1") (pin "20") (pinfunction "A1_20") (pintype "unspecified"))
      (node (ref "RS1") (pin "1") (pinfunction "1_1") (pintype "input"))
      (node (ref "U1") (pin "4") (pinfunction "COL_4") (pintype "unspecified"))
    )
    (net (code "6") (name "A2") (class "Default")
      (node (ref "CIN2") (pin "2") (pinfunction "2_2") (pintype "unspecified"))
      (node (ref "H2") (pin "10") (pinfunction "10_10") (pintype "unspecified"))
      (node (ref "J1") (pin "21") (pinfunction "A2_21") (pintype "unspecified"))
      (node (ref "RS2") (pin "1") (pinfunction "1_1") (pintype "input"))
      (node (ref "U2") (pin "4") (pinfunction "COL_4") (pintype "unspecified"))
    )
    (net (code "7") (name "A3") (class "Default")
      (node (ref "CIN3") (pin "2") (pinfunction "2_2") (pintype "unspecified"))
      (node (ref "H2") (pin "9") (pinfunction "9_9") (pintype "unspecified"))
      (node (ref "J1") (pin "22") (pinfunction "A3_22") (pintype "unspecified"))
      (node (ref "RS3") (pin "1") (pinfunction "1_1") (pintype "input"))
      (node (ref "U3") (pin "4") (pinfunction "COL_4") (pintype "unspecified"))
    )
    (net (code "8") (name "A4") (class "Default")
      (node (ref "CIN4") (pin "2") (pinfunction "2_2") (pintype "unspecified"))
      (node (ref "H2") (pin "8") (pinfunction "8_8") (pintype "unspecified"))
      (node (ref "J1") (pin "23") (pinfunction "A4_23") (pintype "unspecified"))
      (node (ref "RS4") (pin "1") (pinfunction "1_1") (pintype "input"))
      (node (ref "U4") (pin "4") (pinfunction "COL_4") (pintype "unspecified"))
    )
    (net (code "9") (name "A5") (class "Default")
      (node (ref "CIN5") (pin "2") (pinfunction "2_2") (pintype "unspecified"))
      (node (ref "H2") (pin "7") (pinfunction "7_7") (pintype "unspecified"))
      (node (ref "J1") (pin "24") (pinfunction "A5_24") (pintype "unspecified"))
      (node (ref "RS5") (pin "1") (pinfunction "1_1") (pintype "input"))
      (node (ref "U5") (pin "4") (pinfunction "COL_4") (pintype "unspecified"))
    )
    (net (code "10") (name "A6") (class "Default")
      (node (ref "CIN6") (pin "2") (pinfunction "2_2") (pintype "unspecified"))
      (node (ref "H2") (pin "6") (pinfunction "6_6") (pintype "unspecified"))
      (node (ref "J1") (pin "25") (pinfunction "A6_25") (pintype "unspecified"))
      (node (ref "RS6") (pin "1") (pinfunction "1_1") (pintype "input"))
      (node (ref "U6") (pin "4") (pinfunction "COL_4") (pintype "unspecified"))
    )
    (net (code "11") (name "A7") (class "Default")
      (node (ref "CIN7") (pin "2") (pinfunction "2_2") (pintype "unspecified"))
      (node (ref "H2") (pin "5") (pinfunction "5_5") (pintype "unspecified"))
      (node (ref "J1") (pin "26") (pinfunction "A7_26") (pintype "unspecified"))
      (node (ref "RS7") (pin "1") (pinfunction "1_1") (pintype "input"))
      (node (ref "U7") (pin "4") (pinfunction "COL_4") (pintype "unspecified"))
    )
    (net (code "12") (name "D2") (class "Default")
      (node (ref "FL") (pin "1") (pinfunction "A_1") (pintype "unspecified"))
      (node (ref "FQ") (pin "1") (pinfunction "G_1") (pintype "unspecified"))
      (node (ref "FR1") (pin "2") (pinfunction "2_2") (pintype "input"))
      (node (ref "H1") (pin "5") (pinfunction "5_5") (pintype "unspecified"))
      (node (ref "J1") (pin "5") (pinfunction "D2/INT0_5") (pintype "unspecified"))
    )
    (net (code "13") (name "D3") (class "Default")
      (node (ref "EL") (pin "1") (pinfunction "A_1") (pintype "unspecified"))
      (node (ref "EQ") (pin "1") (pinfunction "G_1") (pintype "unspecified"))
      (node (ref "ER1") (pin "2") (pinfunction "2_2") (pintype "input"))
      (node (ref "H1") (pin "6") (pinfunction "6_6") (pintype "unspecified"))
      (node (ref "J1") (pin "6") (pinfunction "D3/INT1_6") (pintype "unspecified"))
    )
    (net (code "14") (name "D4") (class "Default")
      (node (ref "DL") (pin "1") (pinfunction "A_1") (pintype "unspecified"))
      (node (ref "DQ") (pin "1") (pinfunction "G_1") (pintype "unspecified"))
      (node (ref "DR1") (pin "2") (pinfunction "2_2") (pintype "input"))
      (node (ref "H1") (pin "7") (pinfunction "7_7") (pintype "unspecified"))
      (node (ref "J1") (pin "7") (pinfunction "D4/T0_7") (pintype "unspecified"))
    )
    (net (code "15") (name "D5") (class "Default")
      (node (ref "CL") (pin "1") (pinfunction "A_1") (pintype "unspecified"))
      (node (ref "CQ") (pin "1") (pinfunction "G_1") (pintype "unspecified"))
      (node (ref "CR1") (pin "2") (pinfunction "2_2") (pintype "input"))
      (node (ref "H1") (pin "8") (pinfunction "8_8") (pintype "unspecified"))
      (node (ref "J1") (pin "8") (pinfunction "D5/T1_8") (pintype "unspecified"))
    )
    (net (code "16") (name "D6") (class "Default")
      (node (ref "BL") (pin "1") (pinfunction "A_1") (pintype "unspecified"))
      (node (ref "BQ") (pin "1") (pinfunction "G_1") (pintype "unspecified"))
      (node (ref "BR1") (pin "2") (pinfunction "2_2") (pintype "input"))
      (node (ref "H1") (pin "9") (pinfunction "9_9") (pintype "unspecified"))
      (node (ref "J1") (pin "9") (pinfunction "D6/AIN0_9") (pintype "unspecified"))
    )
    (net (code "17") (name "D7") (class "Default")
      (node (ref "AL") (pin "1") (pinfunction "A_1") (pintype "unspecified"))
      (node (ref "AQ") (pin "1") (pinfunction "G_1") (pintype "unspecified"))
      (node (ref "AR1") (pin "2") (pinfunction "2_2") (pintype "input"))
      (node (ref "H1") (pin "10") (pinfunction "10_10") (pintype "unspecified"))
      (node (ref "J1") (pin "10") (pinfunction "D7/AIN1_10") (pintype "unspecified"))
    )
    (net (code "18") (name "D8") (class "Default")
      (node (ref "GL") (pin "1") (pinfunction "A_1") (pintype "unspecified"))
      (node (ref "GQ") (pin "1") (pinfunction "G_1") (pintype "unspecified"))
      (node (ref "GR1") (pin "2") (pinfunction "2_2") (pintype "input"))
      (node (ref "H1") (pin "11") (pinfunction "11_11") (pintype "unspecified"))
      (node (ref "J1") (pin "11") (pinfunction "D8/ICP_11") (pintype "unspecified"))
    )
    (net (code "19") (name "D9") (class "Default")
      (node (ref "BUZZER1") (pin "1") (pinfunction "+_1") (pintype "unspecified"))
      (node (ref "H1") (pin "12") (pinfunction "12_12") (pintype "unspecified"))
      (node (ref "J1") (pin "12") (pinfunction "D9/0C1_12") (pintype "unspecified"))
    )
    (net (code "20") (name "D10") (class "Default")
      (node (ref "H1") (pin "13") (pinfunction "13_13") (pintype "unspecified"))
      (node (ref "J1") (pin "13") (pinfunction "D10_13") (pintype "unspecified"))
    )
    (net (code "21") (name "D11") (class "Default")
      (node (ref "H1") (pin "14") (pinfunction "14_14") (pintype "unspecified"))
      (node (ref "J1") (pin "14") (pinfunction "D11/MOSI_14") (pintype "unspecified"))
    )
    (net (code "22") (name "D12") (class "Default")
      (node (ref "H1") (pin "15") (pinfunction "15_15") (pintype "unspecified"))
      (node (ref "J1") (pin "15") (pinfunction "D12/MISO_15") (pintype "unspecified"))
    )
    (net (code "23") (name "GND") (class "Default")
      (node (ref "78L05") (pin "2") (pinfunction "GND_2") (pintype "unspecified"))
      (node (ref "ACN") (pin "3") (pinfunction "3_3") (pintype "unspecified"))
      (node (ref "AQ") (pin "2") (pinfunction "S_2") (pintype "unspecified"))
      (node (ref "AR1") (pin "1") (pinfunction "1_1") (pintype "input"))
      (node (ref "AR2") (pin "2") (pinfunction "2_2") (pintype "input"))
      (node (ref "BCN") (pin "3") (pinfunction "3_3") (pintype "unspecified"))
      (node (ref "BQ") (pin "2") (pinfunction "S_2") (pintype "unspecified"))
      (node (ref "BR1") (pin "1") (pinfunction "1_1") (pintype "input"))
      (node (ref "BR2") (pin "2") (pinfunction "2_2") (pintype "input"))
      (node (ref "BUZZER1") (pin "2") (pinfunction "2_2") (pintype "unspecified"))
      (node (ref "C2") (pin "2") (pinfunction "2_2") (pintype "input"))
      (node (ref "C3") (pin "1") (pinfunction "1_1") (pintype "unspecified"))
      (node (ref "C5") (pin "1") (pinfunction "1_1") (pintype "unspecified"))
      (node (ref "CCN") (pin "3") (pinfunction "3_3") (pintype "unspecified"))
      (node (ref "CIN1") (pin "1") (pinfunction "1_1") (pintype "unspecified"))
      (node (ref "CIN2") (pin "1") (pinfunction "1_1") (pintype "unspecified"))
      (node (ref "CIN3") (pin "1") (pinfunction "1_1") (pintype "unspecified"))
      (node (ref "CIN4") (pin "1") (pinfunction "1_1") (pintype "unspecified"))
      (node (ref "CIN5") (pin "1") (pinfunction "1_1") (pintype "unspecified"))
      (node (ref "CIN6") (pin "1") (pinfunction "1_1") (pintype "unspecified"))
      (node (ref "CIN7") (pin "1") (pinfunction "1_1") (pintype "unspecified"))
      (node (ref "CQ") (pin "2") (pinfunction "S_2") (pintype "unspecified"))
      (node (ref "CR1") (pin "1") (pinfunction "1_1") (pintype "input"))
      (node (ref "CR12V") (pin "2") (pinfunction "2_2") (pintype "unspecified"))
      (node (ref "CR2") (pin "2") (pinfunction "2_2") (pintype "input"))
      (node (ref "CR5V") (pin "2") (pinfunction "2_2") (pintype "unspecified"))
      (node (ref "DC2") (pin "2") (pinfunction "2_2") (pintype "unspecified"))
      (node (ref "DCN") (pin "3") (pinfunction "3_3") (pintype "unspecified"))
      (node (ref "DQ") (pin "2") (pinfunction "S_2") (pintype "unspecified"))
      (node (ref "DR1") (pin "1") (pinfunction "1_1") (pintype "input"))
      (node (ref "DR2") (pin "2") (pinfunction "2_2") (pintype "input"))
      (node (ref "ECN") (pin "3") (pinfunction "3_3") (pintype "unspecified"))
      (node (ref "EQ") (pin "2") (pinfunction "S_2") (pintype "unspecified"))
      (node (ref "ER1") (pin "1") (pinfunction "1_1") (pintype "input"))
      (node (ref "ER2") (pin "2") (pinfunction "2_2") (pintype "input"))
      (node (ref "FCN") (pin "3") (pinfunction "3_3") (pintype "unspecified"))
      (node (ref "FQ") (pin "2") (pinfunction "S_2") (pintype "unspecified"))
      (node (ref "FR1") (pin "1") (pinfunction "1_1") (pintype "input"))
      (node (ref "FR2") (pin "2") (pinfunction "2_2") (pintype "input"))
      (node (ref "GCN") (pin "3") (pinfunction "3_3") (pintype "unspecified"))
      (node (ref "GQ") (pin "2") (pinfunction "S_2") (pintype "unspecified"))
      (node (ref "GR1") (pin "1") (pinfunction "1_1") (pintype "input"))
      (node (ref "GR2") (pin "2") (pinfunction "2_2") (pintype "input"))
      (node (ref "H1") (pin "4") (pinfunction "4_4") (pintype "unspecified"))
      (node (ref "H10") (pin "5") (pinfunction "5_5") (pintype "unspecified"))
      (node (ref "H11") (pin "5") (pinfunction "5_5") (pintype "unspecified"))
      (node (ref "H12") (pin "5") (pinfunction "5_5") (pintype "unspecified"))
      (node (ref "H2") (pin "2") (pinfunction "2_2") (pintype "unspecified"))
      (node (ref "H3") (pin "5") (pinfunction "5_5") (pintype "unspecified"))
      (node (ref "H4") (pin "5") (pinfunction "5_5") (pintype "unspecified"))
      (node (ref "H5") (pin "5") (pinfunction "5_5") (pintype "unspecified"))
      (node (ref "H6") (pin "5") (pinfunction "5_5") (pintype "unspecified"))
      (node (ref "H7") (pin "5") (pinfunction "5_5") (pintype "unspecified"))
      (node (ref "H8") (pin "5") (pinfunction "5_5") (pintype "unspecified"))
      (node (ref "H9") (pin "5") (pinfunction "5_5") (pintype "unspecified"))
      (node (ref "J1") (pin "29") (pinfunction "GND_29") (pintype "unspecified"))
      (node (ref "J1") (pin "4") (pinfunction "GND_4") (pintype "unspecified"))
      (node (ref "U1") (pin "3") (pinfunction "EM_3") (pintype "unspecified"))
      (node (ref "U2") (pin "3") (pinfunction "EM_3") (pintype "unspecified"))
      (node (ref "U3") (pin "3") (pinfunction "EM_3") (pintype "unspecified"))
      (node (ref "U4") (pin "3") (pinfunction "EM_3") (pintype "unspecified"))
      (node (ref "U5") (pin "3") (pinfunction "EM_3") (pintype "unspecified"))
      (node (ref "U6") (pin "3") (pinfunction "EM_3") (pintype "unspecified"))
      (node (ref "U7") (pin "3") (pinfunction "EM_3") (pintype "unspecified"))
    )
    (net (code "24") (name "Net-(ACR-Pad1)") (class "Default")
      (node (ref "ACR") (pin "1") (pinfunction "1_1") (pintype "unspecified"))
      (node (ref "AK") (pin "5") (pinfunction "5_5") (pintype "unspecified"))
    )
    (net (code "25") (name "Net-(ACR-Pad2)") (class "Default")
      (node (ref "ACR") (pin "2") (pinfunction "2_2") (pintype "unspecified"))
      (node (ref "AJ1") (pin "2") (pinfunction "2_2") (pintype "bidirectional"))
      (node (ref "AR3") (pin "2") (pinfunction "2_2") (pintype "input"))
    )
    (net (code "26") (name "Net-(AD-A)") (class "Default")
      (node (ref "AD") (pin "2") (pinfunction "A_2") (pintype "unspecified"))
      (node (ref "AK") (pin "4") (pinfunction "4_4") (pintype "unspecified"))
      (node (ref "AQ") (pin "3") (pinfunction "D_3") (pintype "unspecified"))
    )
    (net (code "27") (name "Net-(AJ1-Pad1)") (class "Default")
      (node (ref "AJ1") (pin "1") (pinfunction "1_1") (pintype "bidirectional"))
      (node (ref "AK") (pin "1") (pinfunction "1_1") (pintype "unspecified"))
    )
    (net (code "28") (name "Net-(AK-Pad2)") (class "Default")
      (node (ref "AK") (pin "2") (pinfunction "2_2") (pintype "unspecified"))
      (node (ref "AR3") (pin "1") (pinfunction "1_1") (pintype "input"))
    )
    (net (code "29") (name "Net-(AL-K)") (class "Default")
      (node (ref "AL") (pin "2") (pinfunction "K_2") (pintype "unspecified"))
      (node (ref "AR2") (pin "1") (pinfunction "1_1") (pintype "input"))
    )
    (net (code "30") (name "Net-(ALR-A)") (class "Default")
      (node (ref "ALR") (pin "2") (pinfunction "A_2") (pintype "unspecified"))
      (node (ref "AR4") (pin "2") (pinfunction "2_2") (pintype "input"))
    )
    (net (code "31") (name "Net-(ALR-K)") (class "Default")
      (node (ref "ACN") (pin "2") (pinfunction "2_2") (pintype "unspecified"))
      (node (ref "ALR") (pin "1") (pinfunction "K_1") (pintype "unspecified"))
      (node (ref "RS2") (pin "2") (pinfunction "2_2") (pintype "input"))
    )
    (net (code "32") (name "Net-(BCR-Pad1)") (class "Default")
      (node (ref "BCR") (pin "1") (pinfunction "1_1") (pintype "unspecified"))
      (node (ref "BK") (pin "5") (pinfunction "5_5") (pintype "unspecified"))
    )
    (net (code "33") (name "Net-(BCR-Pad2)") (class "Default")
      (node (ref "BCR") (pin "2") (pinfunction "2_2") (pintype "unspecified"))
      (node (ref "BJ1") (pin "2") (pinfunction "2_2") (pintype "bidirectional"))
      (node (ref "BR3") (pin "2") (pinfunction "2_2") (pintype "input"))
    )
    (net (code "34") (name "Net-(BD-A)") (class "Default")
      (node (ref "BD") (pin "2") (pinfunction "A_2") (pintype "unspecified"))
      (node (ref "BK") (pin "4") (pinfunction "4_4") (pintype "unspecified"))
      (node (ref "BQ") (pin "3") (pinfunction "D_3") (pintype "unspecified"))
    )
    (net (code "35") (name "Net-(BJ1-Pad1)") (class "Default")
      (node (ref "BJ1") (pin "1") (pinfunction "1_1") (pintype "bidirectional"))
      (node (ref "BK") (pin "1") (pinfunction "1_1") (pintype "unspecified"))
    )
    (net (code "36") (name "Net-(BK-Pad2)") (class "Default")
      (node (ref "BK") (pin "2") (pinfunction "2_2") (pintype "unspecified"))
      (node (ref "BR3") (pin "1") (pinfunction "1_1") (pintype "input"))
    )
    (net (code "37") (name "Net-(BL-K)") (class "Default")
      (node (ref "BL") (pin "2") (pinfunction "K_2") (pintype "unspecified"))
      (node (ref "BR2") (pin "1") (pinfunction "1_1") (pintype "input"))
    )
    (net (code "38") (name "Net-(BLR-A)") (class "Default")
      (node (ref "BLR") (pin "2") (pinfunction "A_2") (pintype "unspecified"))
      (node (ref "BR4") (pin "2") (pinfunction "2_2") (pintype "input"))
    )
    (net (code "39") (name "Net-(BLR-K)") (class "Default")
      (node (ref "BCN") (pin "2") (pinfunction "2_2") (pintype "unspecified"))
      (node (ref "BLR") (pin "1") (pinfunction "K_1") (pintype "unspecified"))
      (node (ref "RS3") (pin "2") (pinfunction "2_2") (pintype "input"))
    )
    (net (code "40") (name "Net-(CCR-Pad1)") (class "Default")
      (node (ref "CCR") (pin "1") (pinfunction "1_1") (pintype "unspecified"))
      (node (ref "CK") (pin "5") (pinfunction "5_5") (pintype "unspecified"))
    )
    (net (code "41") (name "Net-(CCR-Pad2)") (class "Default")
      (node (ref "CCR") (pin "2") (pinfunction "2_2") (pintype "unspecified"))
      (node (ref "CJ1") (pin "2") (pinfunction "2_2") (pintype "bidirectional"))
      (node (ref "CR3") (pin "2") (pinfunction "2_2") (pintype "input"))
    )
    (net (code "42") (name "Net-(CD-A)") (class "Default")
      (node (ref "CD") (pin "2") (pinfunction "A_2") (pintype "unspecified"))
      (node (ref "CK") (pin "4") (pinfunction "4_4") (pintype "unspecified"))
      (node (ref "CQ") (pin "3") (pinfunction "D_3") (pintype "unspecified"))
    )
    (net (code "43") (name "Net-(CJ1-Pad1)") (class "Default")
      (node (ref "CJ1") (pin "1") (pinfunction "1_1") (pintype "bidirectional"))
      (node (ref "CK") (pin "1") (pinfunction "1_1") (pintype "unspecified"))
    )
    (net (code "44") (name "Net-(CK-Pad2)") (class "Default")
      (node (ref "CK") (pin "2") (pinfunction "2_2") (pintype "unspecified"))
      (node (ref "CR3") (pin "1") (pinfunction "1_1") (pintype "input"))
    )
    (net (code "45") (name "Net-(CL-K)") (class "Default")
      (node (ref "CL") (pin "2") (pinfunction "K_2") (pintype "unspecified"))
      (node (ref "CR2") (pin "1") (pinfunction "1_1") (pintype "input"))
    )
    (net (code "46") (name "Net-(CLR-A)") (class "Default")
      (node (ref "CLR") (pin "2") (pinfunction "A_2") (pintype "unspecified"))
      (node (ref "CR4") (pin "2") (pinfunction "2_2") (pintype "input"))
    )
    (net (code "47") (name "Net-(CLR-K)") (class "Default")
      (node (ref "CCN") (pin "2") (pinfunction "2_2") (pintype "unspecified"))
      (node (ref "CLR") (pin "1") (pinfunction "K_1") (pintype "unspecified"))
      (node (ref "RS4") (pin "2") (pinfunction "2_2") (pintype "input"))
    )
    (net (code "48") (name "Net-(DCR-Pad1)") (class "Default")
      (node (ref "DCR") (pin "1") (pinfunction "1_1") (pintype "unspecified"))
      (node (ref "DK") (pin "5") (pinfunction "5_5") (pintype "unspecified"))
    )
    (net (code "49") (name "Net-(DCR-Pad2)") (class "Default")
      (node (ref "DCR") (pin "2") (pinfunction "2_2") (pintype "unspecified"))
      (node (ref "DJ1") (pin "2") (pinfunction "2_2") (pintype "bidirectional"))
      (node (ref "DR3") (pin "2") (pinfunction "2_2") (pintype "input"))
    )
    (net (code "50") (name "Net-(DD-A)") (class "Default")
      (node (ref "DD") (pin "2") (pinfunction "A_2") (pintype "unspecified"))
      (node (ref "DK") (pin "4") (pinfunction "4_4") (pintype "unspecified"))
      (node (ref "DQ") (pin "3") (pinfunction "D_3") (pintype "unspecified"))
    )
    (net (code "51") (name "Net-(DJ1-Pad1)") (class "Default")
      (node (ref "DJ1") (pin "1") (pinfunction "1_1") (pintype "bidirectional"))
      (node (ref "DK") (pin "1") (pinfunction "1_1") (pintype "unspecified"))
    )
    (net (code "52") (name "Net-(DK-Pad2)") (class "Default")
      (node (ref "DK") (pin "2") (pinfunction "2_2") (pintype "unspecified"))
      (node (ref "DR3") (pin "1") (pinfunction "1_1") (pintype "input"))
    )
    (net (code "53") (name "Net-(DL-K)") (class "Default")
      (node (ref "DL") (pin "2") (pinfunction "K_2") (pintype "unspecified"))
      (node (ref "DR2") (pin "1") (pinfunction "1_1") (pintype "input"))
    )
    (net (code "54") (name "Net-(DLR-A)") (class "Default")
      (node (ref "DLR") (pin "2") (pinfunction "A_2") (pintype "unspecified"))
      (node (ref "DR4") (pin "2") (pinfunction "2_2") (pintype "input"))
    )
    (net (code "55") (name "Net-(DLR-K)") (class "Default")
      (node (ref "DCN") (pin "2") (pinfunction "2_2") (pintype "unspecified"))
      (node (ref "DLR") (pin "1") (pinfunction "K_1") (pintype "unspecified"))
      (node (ref "RS5") (pin "2") (pinfunction "2_2") (pintype "input"))
    )
    (net (code "56") (name "Net-(DOC1-C)") (class "Default")
      (node (ref "COC1") (pin "2") (pinfunction "2_2") (pintype "unspecified"))
      (node (ref "DOC1") (pin "1") (pinfunction "C_1") (pintype "unspecified"))
      (node (ref "ROC1") (pin "1") (pinfunction "1_1") (pintype "input"))
    )
    (net (code "57") (name "Net-(DOC2-C)") (class "Default")
      (node (ref "COC2") (pin "2") (pinfunction "2_2") (pintype "unspecified"))
      (node (ref "DOC2") (pin "1") (pinfunction "C_1") (pintype "unspecified"))
      (node (ref "ROC2") (pin "1") (pinfunction "1_1") (pintype "input"))
    )
    (net (code "58") (name "Net-(DOC3-C)") (class "Default")
      (node (ref "COC3") (pin "2") (pinfunction "2_2") (pintype "unspecified"))
      (node (ref "DOC3") (pin "1") (pinfunction "C_1") (pintype "unspecified"))
      (node (ref "ROC3") (pin "1") (pinfunction "1_1") (pintype "input"))
    )
    (net (code "59") (name "Net-(DOC4-C)") (class "Default")
      (node (ref "COC4") (pin "2") (pinfunction "2_2") (pintype "unspecified"))
      (node (ref "DOC4") (pin "1") (pinfunction "C_1") (pintype "unspecified"))
      (node (ref "ROC4") (pin "1") (pinfunction "1_1") (pintype "input"))
    )
    (net (code "60") (name "Net-(DOC5-C)") (class "Default")
      (node (ref "COC5") (pin "2") (pinfunction "2_2") (pintype "unspecified"))
      (node (ref "DOC5") (pin "1") (pinfunction "C_1") (pintype "unspecified"))
      (node (ref "ROC5") (pin "1") (pinfunction "1_1") (pintype "input"))
    )
    (net (code "61") (name "Net-(DOC6-C)") (class "Default")
      (node (ref "COC6") (pin "2") (pinfunction "2_2") (pintype "unspecified"))
      (node (ref "DOC6") (pin "1") (pinfunction "C_1") (pintype "unspecified"))
      (node (ref "ROC6") (pin "1") (pinfunction "1_1") (pintype "input"))
    )
    (net (code "62") (name "Net-(DOC7-C)") (class "Default")
      (node (ref "COC7") (pin "2") (pinfunction "2_2") (pintype "unspecified"))
      (node (ref "DOC7") (pin "1") (pinfunction "C_1") (pintype "unspecified"))
      (node (ref "ROC7") (pin "1") (pinfunction "1_1") (pintype "input"))
    )
    (net (code "63") (name "Net-(ECR-Pad1)") (class "Default")
      (node (ref "ECR") (pin "1") (pinfunction "1_1") (pintype "unspecified"))
      (node (ref "EK") (pin "5") (pinfunction "5_5") (pintype "unspecified"))
    )
    (net (code "64") (name "Net-(ECR-Pad2)") (class "Default")
      (node (ref "ECR") (pin "2") (pinfunction "2_2") (pintype "unspecified"))
      (node (ref "EJ1") (pin "2") (pinfunction "2_2") (pintype "bidirectional"))
      (node (ref "ER3") (pin "2") (pinfunction "2_2") (pintype "input"))
    )
    (net (code "65") (name "Net-(ED-A)") (class "Default")
      (node (ref "ED") (pin "2") (pinfunction "A_2") (pintype "unspecified"))
      (node (ref "EK") (pin "4") (pinfunction "4_4") (pintype "unspecified"))
      (node (ref "EQ") (pin "3") (pinfunction "D_3") (pintype "unspecified"))
    )
    (net (code "66") (name "Net-(EJ1-Pad1)") (class "Default")
      (node (ref "EJ1") (pin "1") (pinfunction "1_1") (pintype "bidirectional"))
      (node (ref "EK") (pin "1") (pinfunction "1_1") (pintype "unspecified"))
    )
    (net (code "67") (name "Net-(EK-Pad2)") (class "Default")
      (node (ref "EK") (pin "2") (pinfunction "2_2") (pintype "unspecified"))
      (node (ref "ER3") (pin "1") (pinfunction "1_1") (pintype "input"))
    )
    (net (code "68") (name "Net-(EL-K)") (class "Default")
      (node (ref "EL") (pin "2") (pinfunction "K_2") (pintype "unspecified"))
      (node (ref "ER2") (pin "1") (pinfunction "1_1") (pintype "input"))
    )
    (net (code "69") (name "Net-(ELR-A)") (class "Default")
      (node (ref "ELR") (pin "2") (pinfunction "A_2") (pintype "unspecified"))
      (node (ref "ER4") (pin "2") (pinfunction "2_2") (pintype "input"))
    )
    (net (code "70") (name "Net-(ELR-K)") (class "Default")
      (node (ref "ECN") (pin "2") (pinfunction "2_2") (pintype "unspecified"))
      (node (ref "ELR") (pin "1") (pinfunction "K_1") (pintype "unspecified"))
      (node (ref "RS6") (pin "2") (pinfunction "2_2") (pintype "input"))
    )
    (net (code "71") (name "Net-(FCR-Pad1)") (class "Default")
      (node (ref "FCR") (pin "1") (pinfunction "1_1") (pintype "unspecified"))
      (node (ref "FK") (pin "5") (pinfunction "5_5") (pintype "unspecified"))
    )
    (net (code "72") (name "Net-(FCR-Pad2)") (class "Default")
      (node (ref "FCR") (pin "2") (pinfunction "2_2") (pintype "unspecified"))
      (node (ref "FJ1") (pin "2") (pinfunction "2_2") (pintype "bidirectional"))
      (node (ref "FR3") (pin "2") (pinfunction "2_2") (pintype "input"))
    )
    (net (code "73") (name "Net-(FD-A)") (class "Default")
      (node (ref "FD") (pin "2") (pinfunction "A_2") (pintype "unspecified"))
      (node (ref "FK") (pin "4") (pinfunction "4_4") (pintype "unspecified"))
      (node (ref "FQ") (pin "3") (pinfunction "D_3") (pintype "unspecified"))
    )
    (net (code "74") (name "Net-(FJ1-Pad1)") (class "Default")
      (node (ref "FJ1") (pin "1") (pinfunction "1_1") (pintype "bidirectional"))
      (node (ref "FK") (pin "1") (pinfunction "1_1") (pintype "unspecified"))
    )
    (net (code "75") (name "Net-(FK-Pad2)") (class "Default")
      (node (ref "FK") (pin "2") (pinfunction "2_2") (pintype "unspecified"))
      (node (ref "FR3") (pin "1") (pinfunction "1_1") (pintype "input"))
    )
    (net (code "76") (name "Net-(FL-K)") (class "Default")
      (node (ref "FL") (pin "2") (pinfunction "K_2") (pintype "unspecified"))
      (node (ref "FR2") (pin "1") (pinfunction "1_1") (pintype "input"))
    )
    (net (code "77") (name "Net-(FLR-A)") (class "Default")
      (node (ref "FLR") (pin "2") (pinfunction "A_2") (pintype "unspecified"))
      (node (ref "FR4") (pin "2") (pinfunction "2_2") (pintype "input"))
    )
    (net (code "78") (name "Net-(FLR-K)") (class "Default")
      (node (ref "FCN") (pin "2") (pinfunction "2_2") (pintype "unspecified"))
      (node (ref "FLR") (pin "1") (pinfunction "K_1") (pintype "unspecified"))
      (node (ref "RS7") (pin "2") (pinfunction "2_2") (pintype "input"))
    )
    (net (code "79") (name "Net-(GCR-Pad1)") (class "Default")
      (node (ref "GCR") (pin "1") (pinfunction "1_1") (pintype "unspecified"))
      (node (ref "GK") (pin "5") (pinfunction "5_5") (pintype "unspecified"))
    )
    (net (code "80") (name "Net-(GCR-Pad2)") (class "Default")
      (node (ref "GCR") (pin "2") (pinfunction "2_2") (pintype "unspecified"))
      (node (ref "GJ1") (pin "2") (pinfunction "2_2") (pintype "bidirectional"))
      (node (ref "GR3") (pin "2") (pinfunction "2_2") (pintype "input"))
    )
    (net (code "81") (name "Net-(GD-A)") (class "Default")
      (node (ref "GD") (pin "2") (pinfunction "A_2") (pintype "unspecified"))
      (node (ref "GK") (pin "4") (pinfunction "4_4") (pintype "unspecified"))
      (node (ref "GQ") (pin "3") (pinfunction "D_3") (pintype "unspecified"))
    )
    (net (code "82") (name "Net-(GJ1-Pad1)") (class "Default")
      (node (ref "GJ1") (pin "1") (pinfunction "1_1") (pintype "bidirectional"))
      (node (ref "GK") (pin "1") (pinfunction "1_1") (pintype "unspecified"))
    )
    (net (code "83") (name "Net-(GK-Pad2)") (class "Default")
      (node (ref "GK") (pin "2") (pinfunction "2_2") (pintype "unspecified"))
      (node (ref "GR3") (pin "1") (pinfunction "1_1") (pintype "input"))
    )
    (net (code "84") (name "Net-(GL-K)") (class "Default")
      (node (ref "GL") (pin "2") (pinfunction "K_2") (pintype "unspecified"))
      (node (ref "GR2") (pin "1") (pinfunction "1_1") (pintype "input"))
    )
    (net (code "85") (name "Net-(GLR-A)") (class "Default")
      (node (ref "GLR") (pin "2") (pinfunction "A_2") (pintype "unspecified"))
      (node (ref "GR4") (pin "2") (pinfunction "2_2") (pintype "input"))
    )
    (net (code "86") (name "Net-(GLR-K)") (class "Default")
      (node (ref "GCN") (pin "2") (pinfunction "2_2") (pintype "unspecified"))
      (node (ref "GLR") (pin "1") (pinfunction "K_1") (pintype "unspecified"))
      (node (ref "RS1") (pin "2") (pinfunction "2_2") (pintype "input"))
    )
    (net (code "87") (name "Net-(H1-Pad3)") (class "Default")
      (node (ref "H1") (pin "3") (pinfunction "3_3") (pintype "unspecified"))
      (node (ref "J1") (pin "3") (pinfunction "RESET_3") (pintype "unspecified"))
    )
    (net (code "88") (name "Net-(H2-Pad3)") (class "Default")
      (node (ref "H2") (pin "3") (pinfunction "3_3") (pintype "unspecified"))
      (node (ref "J1") (pin "28") (pinfunction "RESET_28") (pintype "unspecified"))
    )
    (net (code "89") (name "Net-(J1-AREF)") (class "Default")
      (node (ref "H2") (pin "13") (pinfunction "13_13") (pintype "unspecified"))
      (node (ref "J1") (pin "18") (pinfunction "AREF_18") (pintype "unspecified"))
    )
    (net (code "90") (name "Net-(J1-D0{slash}RX)") (class "Default")
      (node (ref "H1") (pin "2") (pinfunction "2_2") (pintype "unspecified"))
      (node (ref "J1") (pin "2") (pinfunction "D0/RX_2") (pintype "unspecified"))
    )
    (net (code "91") (name "Net-(J1-D1{slash}TX)") (class "Default")
      (node (ref "H1") (pin "1") (pinfunction "1_1") (pintype "unspecified"))
      (node (ref "J1") (pin "1") (pinfunction "D1/TX_1") (pintype "unspecified"))
    )
    (net (code "92") (name "Net-(J1-SCK{slash}D13)") (class "Default")
      (node (ref "H2") (pin "15") (pinfunction "15_15") (pintype "unspecified"))
      (node (ref "J1") (pin "16") (pinfunction "SCK/D13_16") (pintype "unspecified"))
    )
    (net (code "93") (name "Net-(U1-AN)") (class "Default")
      (node (ref "ROC1") (pin "2") (pinfunction "2_2") (pintype "input"))
      (node (ref "U1") (pin "1") (pinfunction "AN_1") (pintype "unspecified"))
    )
    (net (code "94") (name "Net-(U2-AN)") (class "Default")
      (node (ref "ROC2") (pin "2") (pinfunction "2_2") (pintype "input"))
      (node (ref "U2") (pin "1") (pinfunction "AN_1") (pintype "unspecified"))
    )
    (net (code "95") (name "Net-(U3-AN)") (class "Default")
      (node (ref "ROC3") (pin "2") (pinfunction "2_2") (pintype "input"))
      (node (ref "U3") (pin "1") (pinfunction "AN_1") (pintype "unspecified"))
    )
    (net (code "96") (name "Net-(U4-AN)") (class "Default")
      (node (ref "ROC4") (pin "2") (pinfunction "2_2") (pintype "input"))
      (node (ref "U4") (pin "1") (pinfunction "AN_1") (pintype "unspecified"))
    )
    (net (code "97") (name "Net-(U5-AN)") (class "Default")
      (node (ref "ROC5") (pin "2") (pinfunction "2_2") (pintype "input"))
      (node (ref "U5") (pin "1") (pinfunction "AN_1") (pintype "unspecified"))
    )
    (net (code "98") (name "Net-(U6-AN)") (class "Default")
      (node (ref "ROC6") (pin "2") (pinfunction "2_2") (pintype "input"))
      (node (ref "U6") (pin "1") (pinfunction "AN_1") (pintype "unspecified"))
    )
    (net (code "99") (name "Net-(U7-AN)") (class "Default")
      (node (ref "ROC7") (pin "2") (pinfunction "2_2") (pintype "input"))
      (node (ref "U7") (pin "1") (pinfunction "AN_1") (pintype "unspecified"))
    )
    (net (code "100") (name "TR_1") (class "Default")
      (node (ref "ACON1") (pin "1") (pinfunction "1_1") (pintype "unspecified"))
      (node (ref "DOC1") (pin "2") (pinfunction "A_2") (pintype "unspecified"))
    )
    (net (code "101") (name "TR_2") (class "Default")
      (node (ref "ACON2") (pin "1") (pinfunction "1_1") (pintype "unspecified"))
      (node (ref "DOC2") (pin "2") (pinfunction "A_2") (pintype "unspecified"))
    )
    (net (code "102") (name "TR_3") (class "Default")
      (node (ref "ACON3") (pin "1") (pinfunction "1_1") (pintype "unspecified"))
      (node (ref "DOC3") (pin "2") (pinfunction "A_2") (pintype "unspecified"))
    )
    (net (code "103") (name "TR_4") (class "Default")
      (node (ref "ACON4") (pin "1") (pinfunction "1_1") (pintype "unspecified"))
      (node (ref "DOC4") (pin "2") (pinfunction "A_2") (pintype "unspecified"))
    )
    (net (code "104") (name "TR_5") (class "Default")
      (node (ref "ACON5") (pin "1") (pinfunction "1_1") (pintype "unspecified"))
      (node (ref "DOC5") (pin "2") (pinfunction "A_2") (pintype "unspecified"))
    )
    (net (code "105") (name "TR_6") (class "Default")
      (node (ref "ACON6") (pin "1") (pinfunction "1_1") (pintype "unspecified"))
      (node (ref "DOC6") (pin "2") (pinfunction "A_2") (pintype "unspecified"))
    )
    (net (code "106") (name "TR_7") (class "Default")
      (node (ref "ACON7") (pin "1") (pinfunction "1_1") (pintype "unspecified"))
      (node (ref "DOC7") (pin "2") (pinfunction "A_2") (pintype "unspecified"))
    )
    (net (code "107") (name "TR_COM") (class "Default")
      (node (ref "ACON1") (pin "2") (pinfunction "2_2") (pintype "unspecified"))
      (node (ref "ACON2") (pin "2") (pinfunction "2_2") (pintype "unspecified"))
      (node (ref "ACON3") (pin "2") (pinfunction "2_2") (pintype "unspecified"))
      (node (ref "ACON4") (pin "2") (pinfunction "2_2") (pintype "unspecified"))
      (node (ref "ACON5") (pin "2") (pinfunction "2_2") (pintype "unspecified"))
      (node (ref "ACON6") (pin "2") (pinfunction "2_2") (pintype "unspecified"))
      (node (ref "ACON7") (pin "2") (pinfunction "2_2") (pintype "unspecified"))
      (node (ref "COC1") (pin "1") (pinfunction "1_1") (pintype "unspecified"))
      (node (ref "COC2") (pin "1") (pinfunction "1_1") (pintype "unspecified"))
      (node (ref "COC3") (pin "1") (pinfunction "1_1") (pintype "unspecified"))
      (node (ref "COC4") (pin "1") (pinfunction "1_1") (pintype "unspecified"))
      (node (ref "COC5") (pin "1") (pinfunction "1_1") (pintype "unspecified"))
      (node (ref "COC6") (pin "1") (pinfunction "1_1") (pintype "unspecified"))
      (node (ref "COC7") (pin "1") (pinfunction "1_1") (pintype "unspecified"))
      (node (ref "U1") (pin "2") (pinfunction "CAT_2") (pintype "unspecified"))
      (node (ref "U2") (pin "2") (pinfunction "CAT_2") (pintype "unspecified"))
      (node (ref "U3") (pin "2") (pinfunction "CAT_2") (pintype "unspecified"))
      (node (ref "U4") (pin "2") (pinfunction "CAT_2") (pintype "unspecified"))
      (node (ref "U5") (pin "2") (pinfunction "CAT_2") (pintype "unspecified"))
      (node (ref "U6") (pin "2") (pinfunction "CAT_2") (pintype "unspecified"))
      (node (ref "U7") (pin "2") (pinfunction "CAT_2") (pintype "unspecified"))
    )
    (net (code "108") (name "VIN") (class "Default")
      (node (ref "78L05") (pin "1") (pinfunction "VO_1") (pintype "unspecified"))
      (node (ref "ACN") (pin "1") (pinfunction "1_1") (pintype "unspecified"))
      (node (ref "AR4") (pin "1") (pinfunction "1_1") (pintype "input"))
      (node (ref "BCN") (pin "1") (pinfunction "1_1") (pintype "unspecified"))
      (node (ref "BR4") (pin "1") (pinfunction "1_1") (pintype "input"))
      (node (ref "C3") (pin "2") (pinfunction "2_2") (pintype "unspecified"))
      (node (ref "CCN") (pin "1") (pinfunction "1_1") (pintype "unspecified"))
      (node (ref "CR4") (pin "1") (pinfunction "1_1") (pintype "input"))
      (node (ref "CR5V") (pin "1") (pinfunction "1_1") (pintype "unspecified"))
      (node (ref "DCN") (pin "1") (pinfunction "1_1") (pintype "unspecified"))
      (node (ref "DR4") (pin "1") (pinfunction "1_1") (pintype "input"))
      (node (ref "ECN") (pin "1") (pinfunction "1_1") (pintype "unspecified"))
      (node (ref "ER4") (pin "1") (pinfunction "1_1") (pintype "input"))
      (node (ref "FCN") (pin "1") (pinfunction "1_1") (pintype "unspecified"))
      (node (ref "FR4") (pin "1") (pinfunction "1_1") (pintype "input"))
      (node (ref "GCN") (pin "1") (pinfunction "1_1") (pintype "unspecified"))
      (node (ref "GR4") (pin "1") (pinfunction "1_1") (pintype "input"))
      (node (ref "H10") (pin "1") (pinfunction "1_1") (pintype "unspecified"))
      (node (ref "H11") (pin "1") (pinfunction "1_1") (pintype "unspecified"))
      (node (ref "H2") (pin "1") (pinfunction "1_1") (pintype "unspecified"))
      (node (ref "H7") (pin "1") (pinfunction "1_1") (pintype "unspecified"))
      (node (ref "H8") (pin "1") (pinfunction "1_1") (pintype "unspecified"))
      (node (ref "H9") (pin "1") (pinfunction "1_1") (pintype "unspecified"))
      (node (ref "J1") (pin "30") (pinfunction "VIN_30") (pintype "unspecified"))
    )
    (net (code "109") (name "unconnected-(DC2-Pad3)") (class "Default")
      (node (ref "DC2") (pin "3") (pinfunction "3_3") (pintype "unspecified"))
    )
    (net (code "110") (name "unconnected-(H3-Pad2)") (class "Default")
      (node (ref "H3") (pin "2") (pinfunction "2_2") (pintype "unspecified"))
    )
    (net (code "111") (name "unconnected-(H3-Pad3)") (class "Default")
      (node (ref "H3") (pin "3") (pinfunction "3_3") (pintype "unspecified"))
    )
    (net (code "112") (name "unconnected-(H3-Pad4)") (class "Default")
      (node (ref "H3") (pin "4") (pinfunction "4_4") (pintype "unspecified"))
    )
    (net (code "113") (name "unconnected-(H4-Pad2)") (class "Default")
      (node (ref "H4") (pin "2") (pinfunction "2_2") (pintype "unspecified"))
    )
    (net (code "114") (name "unconnected-(H4-Pad3)") (class "Default")
      (node (ref "H4") (pin "3") (pinfunction "3_3") (pintype "unspecified"))
    )
    (net (code "115") (name "unconnected-(H4-Pad4)") (class "Default")
      (node (ref "H4") (pin "4") (pinfunction "4_4") (pintype "unspecified"))
    )
    (net (code "116") (name "unconnected-(H5-Pad2)") (class "Default")
      (node (ref "H5") (pin "2") (pinfunction "2_2") (pintype "unspecified"))
    )
    (net (code "117") (name "unconnected-(H5-Pad3)") (class "Default")
      (node (ref "H5") (pin "3") (pinfunction "3_3") (pintype "unspecified"))
    )
    (net (code "118") (name "unconnected-(H5-Pad4)") (class "Default")
      (node (ref "H5") (pin "4") (pinfunction "4_4") (pintype "unspecified"))
    )
    (net (code "119") (name "unconnected-(H6-Pad2)") (class "Default")
      (node (ref "H6") (pin "2") (pinfunction "2_2") (pintype "unspecified"))
    )
    (net (code "120") (name "unconnected-(H6-Pad3)") (class "Default")
      (node (ref "H6") (pin "3") (pinfunction "3_3") (pintype "unspecified"))
    )
    (net (code "121") (name "unconnected-(H6-Pad4)") (class "Default")
      (node (ref "H6") (pin "4") (pinfunction "4_4") (pintype "unspecified"))
    )
    (net (code "122") (name "unconnected-(H7-Pad2)") (class "Default")
      (node (ref "H7") (pin "2") (pinfunction "2_2") (pintype "unspecified"))
    )
    (net (code "123") (name "unconnected-(H7-Pad3)") (class "Default")
      (node (ref "H7") (pin "3") (pinfunction "3_3") (pintype "unspecified"))
    )
    (net (code "124") (name "unconnected-(H7-Pad4)") (class "Default")
      (node (ref "H7") (pin "4") (pinfunction "4_4") (pintype "unspecified"))
    )
    (net (code "125") (name "unconnected-(H8-Pad2)") (class "Default")
      (node (ref "H8") (pin "2") (pinfunction "2_2") (pintype "unspecified"))
    )
    (net (code "126") (name "unconnected-(H8-Pad3)") (class "Default")
      (node (ref "H8") (pin "3") (pinfunction "3_3") (pintype "unspecified"))
    )
    (net (code "127") (name "unconnected-(H8-Pad4)") (class "Default")
      (node (ref "H8") (pin "4") (pinfunction "4_4") (pintype "unspecified"))
    )
    (net (code "128") (name "unconnected-(H9-Pad2)") (class "Default")
      (node (ref "H9") (pin "2") (pinfunction "2_2") (pintype "unspecified"))
    )
    (net (code "129") (name "unconnected-(H9-Pad3)") (class "Default")
      (node (ref "H9") (pin "3") (pinfunction "3_3") (pintype "unspecified"))
    )
    (net (code "130") (name "unconnected-(H9-Pad4)") (class "Default")
      (node (ref "H9") (pin "4") (pinfunction "4_4") (pintype "unspecified"))
    )
    (net (code "131") (name "unconnected-(H10-Pad2)") (class "Default")
      (node (ref "H10") (pin "2") (pinfunction "2_2") (pintype "unspecified"))
    )
    (net (code "132") (name "unconnected-(H10-Pad3)") (class "Default")
      (node (ref "H10") (pin "3") (pinfunction "3_3") (pintype "unspecified"))
    )
    (net (code "133") (name "unconnected-(H10-Pad4)") (class "Default")
      (node (ref "H10") (pin "4") (pinfunction "4_4") (pintype "unspecified"))
    )
    (net (code "134") (name "unconnected-(H11-Pad2)") (class "Default")
      (node (ref "H11") (pin "2") (pinfunction "2_2") (pintype "unspecified"))
    )
    (net (code "135") (name "unconnected-(H11-Pad3)") (class "Default")
      (node (ref "H11") (pin "3") (pinfunction "3_3") (pintype "unspecified"))
    )
    (net (code "136") (name "unconnected-(H11-Pad4)") (class "Default")
      (node (ref "H11") (pin "4") (pinfunction "4_4") (pintype "unspecified"))
    )
    (net (code "137") (name "unconnected-(H12-Pad2)") (class "Default")
      (node (ref "H12") (pin "2") (pinfunction "2_2") (pintype "unspecified"))
    )
    (net (code "138") (name "unconnected-(H12-Pad3)") (class "Default")
      (node (ref "H12") (pin "3") (pinfunction "3_3") (pintype "unspecified"))
    )
    (net (code "139") (name "unconnected-(H12-Pad4)") (class "Default")
      (node (ref "H12") (pin "4") (pinfunction "4_4") (pintype "unspecified"))
    )
  )
)
